# 555_LED_BLINKER_PCB_BOARD1.net
KiCad netlist of a schematic drawn in Altium Designer
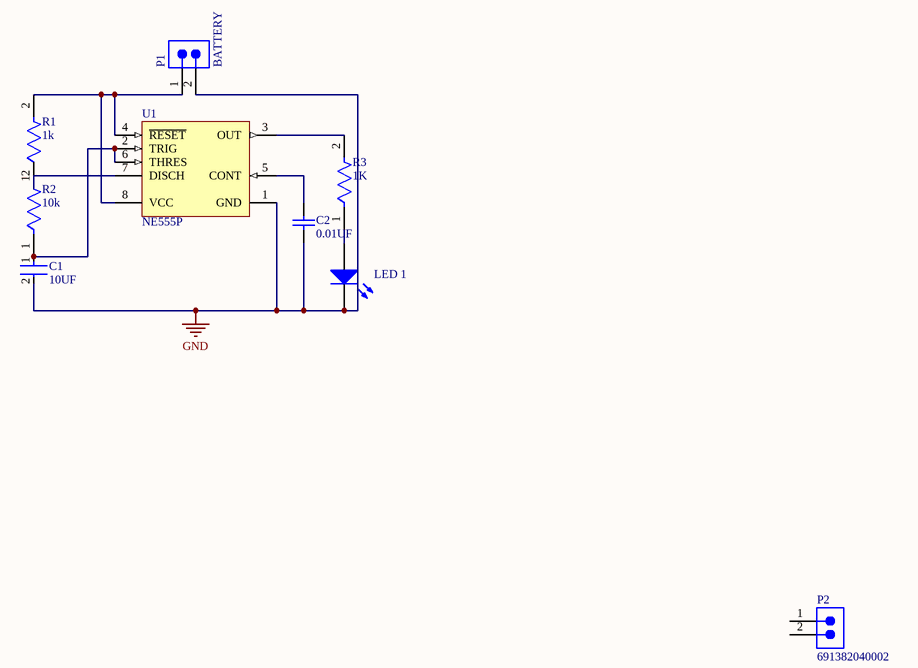
[diagram p0: 555 LED BLINKER PCB BOARD1.SchDoc]

(export (version "E")
  (design (tool "Eeschema 10.0.6"))
  (components
    (comp (ref "C1")
      (value "10UF")
      (footprint "FP-CL31-IPC_C")
      (description "Cap Ceramic 10uF 16V X5R ±10% SMD 1206 +85°C Embossed T/R")
      (fields (field (name "TOLERANCE") "10%"))
      (libsource (lib "Altium Content Vault") (part "b4654b650e69147ec39a6b967a45e02"))
    )
    (comp (ref "C2")
      (value "0.01UF")
      (footprint "CAPC1608X92X38LL15T08")
      (fields (field (name "PART NUMBER") "VJ0603Y103JXAAC") (field (name "MANUFACTURER") "Vitramon"))
      (libsource (lib "Altium Content Vault") (part "CAP"))
    )
    (comp (ref "LED 1")
      (value "LED")
      (description "Light-Emitting Diode")
      (libsource (lib "Simulation Generic Components") (part "LED"))
    )
    (comp (ref "P1")
      (value "BATTERY")
      (footprint "691382040002")
      (description "Terminal Block, 2.50MM Pitch, Horizontal Pcb Header, Flanges, 300VAC, 2 Pins")
      (fields (field (name "VOLTAGE") "300V"))
      (libsource (lib "Altium Content Vault") (part "TBL - 1R - 02P - Male"))
    )
    (comp (ref "P2")
      (value "691382040002")
      (footprint "691382040002")
      (description "Terminal Block, 2.50MM Pitch, Horizontal Pcb Header, Flanges, 300VAC, 2 Pins")
      (fields (field (name "VOLTAGE") "300V"))
      (libsource (lib "Altium Content Vault") (part "TBL - 1R - 02P - Male"))
    )
    (comp (ref "R1")
      (value "1k")
      (footprint "FP-RN73R2B-MFG")
      (description "1kΩ ±1% 0.25W, 1/4W Chip Resistor 1206 (3216 Metric) Moisture Resistant Thin Film")
      (libsource (lib "Altium Content Vault") (part "1029c3af85768c4190bb7ad29bc67b5"))
    )
    (comp (ref "R2")
      (value "10k")
      (footprint "FP-AT0805-MFG")
      (description "Thin Film Chip Resistors Automotive Grade 10kΩ 0.5% 50ppm/°C 0805")
      (fields (field (name "TOLERANCE") "0.5%"))
      (libsource (lib "Altium Content Vault") (part "1029c3af85768c4190bb7ad29bc67b5"))
    )
    (comp (ref "R3")
      (value "1K")
      (footprint "FP-RN73R2B-MFG")
      (description "1kΩ ±1% 0.25W, 1/4W Chip Resistor 1206 (3216 Metric) Moisture Resistant Thin Film")
      (libsource (lib "Altium Content Vault") (part "1029c3af85768c4190bb7ad29bc67b5"))
    )
    (comp (ref "U1")
      (value "NE555P")
      (footprint "P0008A")
      (description "Precision Timer, 4.5 to 16 V, 0 to 70 degC, 8-Pin DIP, Pb-Free, Tube")
      (fields (field (name "MANUFACTURER") "TexasInstruments"))
      (libsource (lib "Altium Content Vault") (part "TI-NE555-P8"))
    )
  )
  (nets
    (net (code "1") (name "GND") (class "Default")
      (node (ref "C1") (pin "2") (pinfunction "2_2") (pintype "passive"))
      (node (ref "C2") (pin "1") (pinfunction "1_1") (pintype "passive"))
      (node (ref "LED 1") (pin "2") (pinfunction "K_2") (pintype "passive"))
      (node (ref "P1") (pin "2") (pinfunction "2_2") (pintype "passive"))
      (node (ref "U1") (pin "1") (pinfunction "GND_1") (pintype "power_in"))
    )
    (net (code "2") (name "Net-(LED 1-A)") (class "Default")
      (node (ref "LED 1") (pin "1") (pinfunction "A_1") (pintype "passive"))
      (node (ref "R3") (pin "1") (pinfunction "1_1") (pintype "passive"))
    )
    (net (code "3") (name "Net-(U1-CONT)") (class "Default")
      (node (ref "C2") (pin "2") (pinfunction "2_2") (pintype "passive"))
      (node (ref "U1") (pin "5") (pinfunction "CONT_5") (pintype "input"))
    )
    (net (code "4") (name "Net-(U1-DISCH)") (class "Default")
      (node (ref "R1") (pin "1") (pinfunction "1_1") (pintype "passive"))
      (node (ref "U1") (pin "7") (pinfunction "DISCH_7") (pintype "open_collector"))
    )
    (net (code "5") (name "Net-(U1-OUT)") (class "Default")
      (node (ref "R3") (pin "2") (pinfunction "2_2") (pintype "passive"))
      (node (ref "U1") (pin "3") (pinfunction "OUT_3") (pintype "output"))
    )
    (net (code "6") (name "Net-(U1-THRES)") (class "Default")
      (node (ref "C1") (pin "1") (pinfunction "1_1") (pintype "passive"))
      (node (ref "R2") (pin "1") (pinfunction "1_1") (pintype "passive"))
      (node (ref "U1") (pin "2") (pinfunction "TRIG_2") (pintype "input"))
      (node (ref "U1") (pin "6") (pinfunction "THRES_6") (pintype "input"))
    )
    (net (code "7") (name "Net-(U1-VCC)") (class "Default")
      (node (ref "P1") (pin "1") (pinfunction "1_1") (pintype "passive"))
      (node (ref "R1") (pin "2") (pinfunction "2_2") (pintype "passive"))
      (node (ref "U1") (pin "4") (pinfunction "~{RESET}_4") (pintype "input"))
      (node (ref "U1") (pin "8") (pinfunction "VCC_8") (pintype "power_in"))
    )
    (net (code "8") (name "unconnected-(P2-Pad1)") (class "Default")
      (node (ref "P2") (pin "1") (pinfunction "1_1") (pintype "passive"))
    )
    (net (code "9") (name "unconnected-(P2-Pad2)") (class "Default")
      (node (ref "P2") (pin "2") (pinfunction "2_2") (pintype "passive"))
    )
    (net (code "10") (name "unconnected-(R2-Pad2)") (class "Default")
      (node (ref "R2") (pin "2") (pinfunction "2_2") (pintype "passive"))
    )
  )
)
